# Orbiter_ENCODER_V4_0.net
KiCad netlist of a schematic drawn in EAGLE
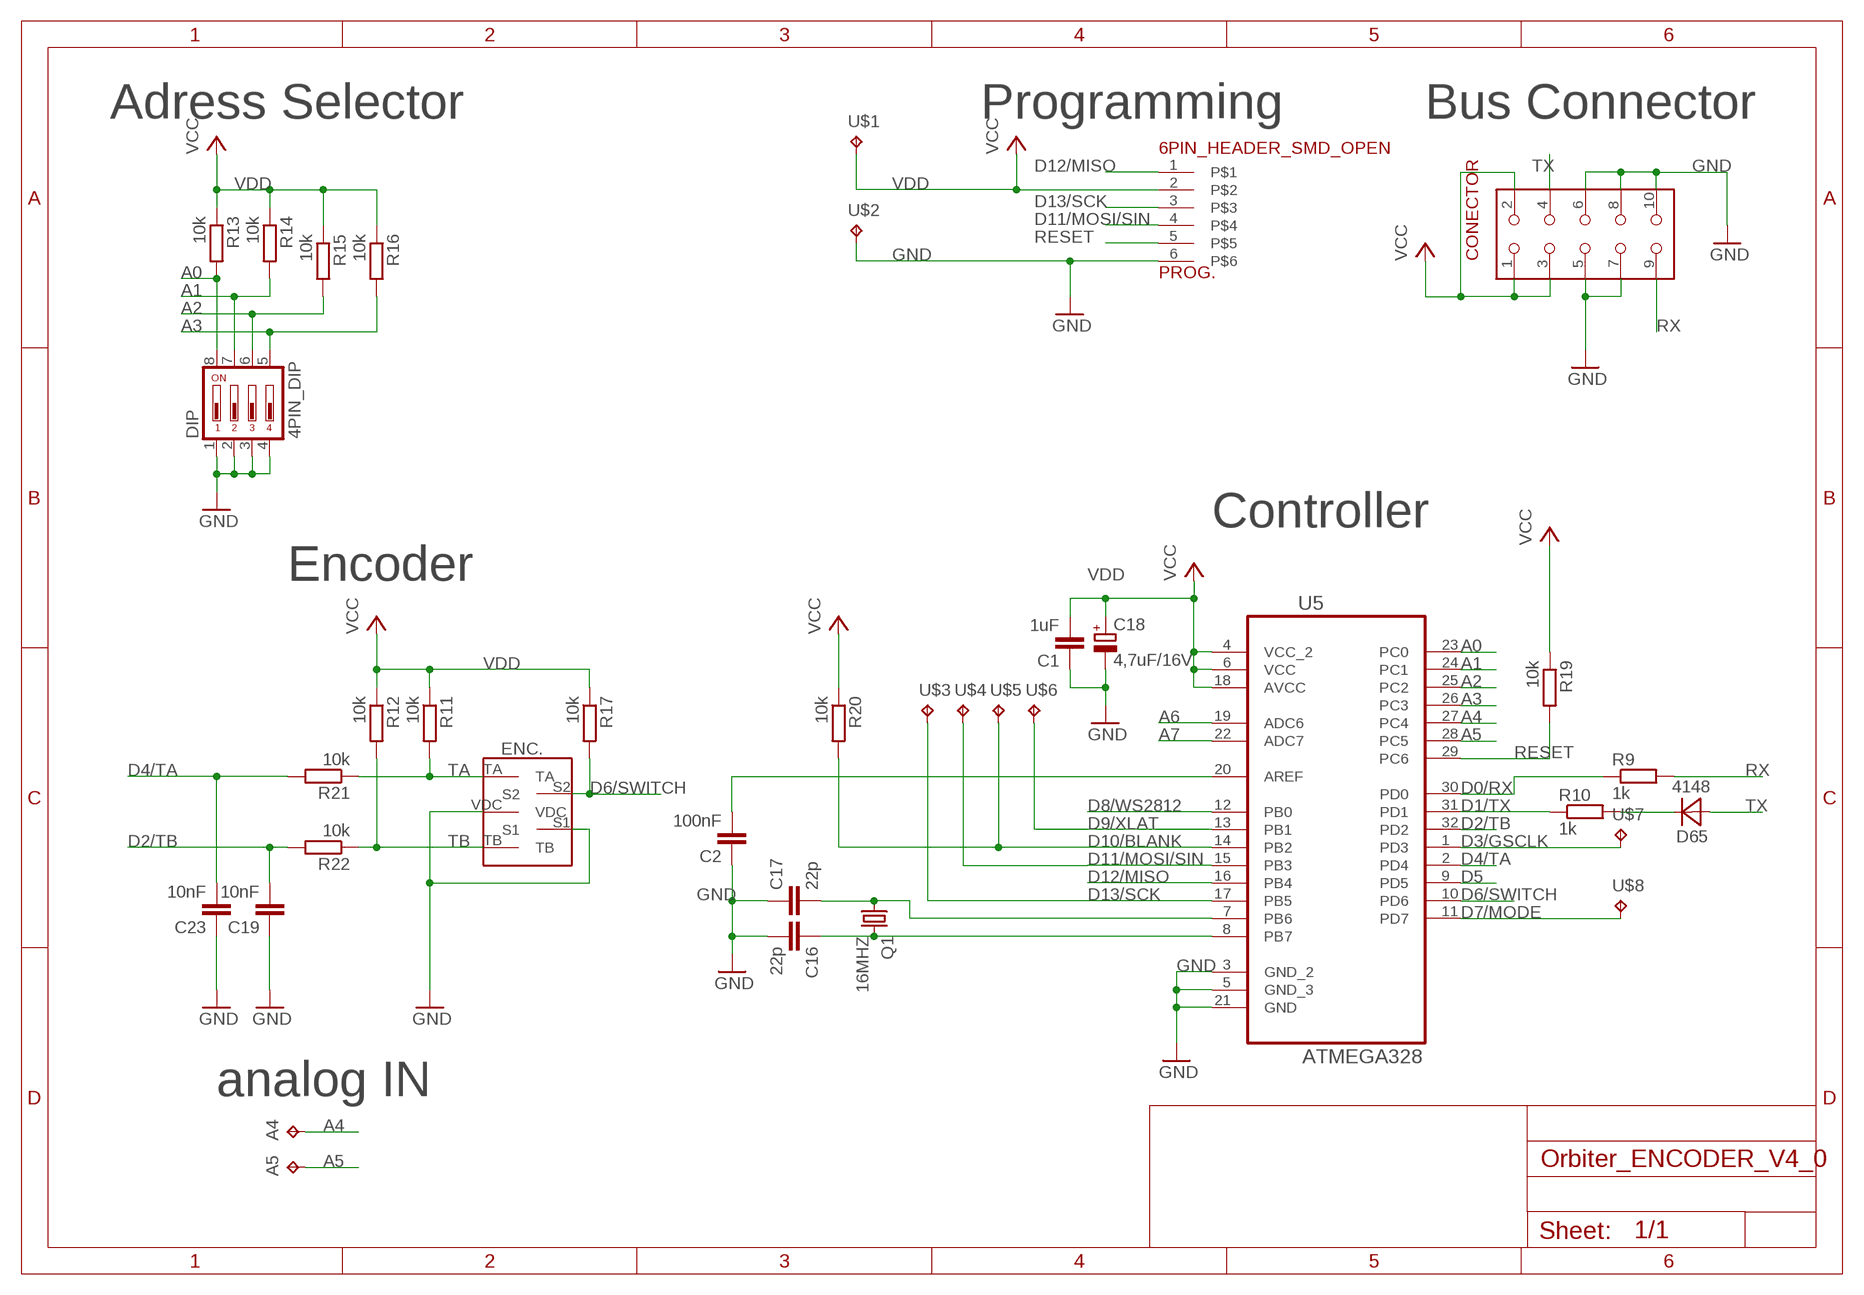
[diagram p0: schematic, sheet 1]

(export (version "E")
  (design (tool "Eeschema 10.0.6"))
  (components
    (comp (ref "A4")
      (value "TP")
      (footprint "eagle-import:OVAL_PAD")
      (libsource (lib "eagle-import") (part "TP"))
    )
    (comp (ref "A5")
      (value "TP")
      (footprint "eagle-import:OVAL_PAD")
      (libsource (lib "eagle-import") (part "TP"))
    )
    (comp (ref "C1")
      (value "1uF")
      (footprint "eagle-import:C0603")
      (libsource (lib "eagle-import") (part "CAPACITOR{dblquote}"))
    )
    (comp (ref "C2")
      (value "100nF")
      (footprint "eagle-import:C0603")
      (libsource (lib "eagle-import") (part "CAPACITOR{dblquote}"))
    )
    (comp (ref "C16")
      (value "22p")
      (footprint "eagle-import:C0603")
      (libsource (lib "eagle-import") (part "CAPACITOR{dblquote}"))
    )
    (comp (ref "C17")
      (value "22p")
      (footprint "eagle-import:C0603")
      (libsource (lib "eagle-import") (part "CAPACITOR{dblquote}"))
    )
    (comp (ref "C18")
      (value "4,7uF/16V")
      (footprint "eagle-import:153CLV-0605")
      (libsource (lib "eagle-import") (part "SMD_ELCTROLYTIC"))
    )
    (comp (ref "C19")
      (value "10nF")
      (footprint "eagle-import:C0603")
      (libsource (lib "eagle-import") (part "CAPACITOR{dblquote}"))
    )
    (comp (ref "C23")
      (value "10nF")
      (footprint "eagle-import:C0603")
      (libsource (lib "eagle-import") (part "CAPACITOR{dblquote}"))
    )
    (comp (ref "CONECTOR")
      (value "10PIN_HEADER_SMD")
      (footprint "eagle-import:87832-10")
      (libsource (lib "eagle-import") (part "10PIN_HEADER_SMD"))
    )
    (comp (ref "D65")
      (value "4148")
      (footprint "eagle-import:SOD323-R")
      (libsource (lib "eagle-import") (part "4148"))
    )
    (comp (ref "DIP")
      (value "4PIN_DIP")
      (footprint "eagle-import:CTS-219-04")
      (libsource (lib "eagle-import") (part "4PIN_DIP"))
    )
    (comp (ref "ENC.")
      (value "BOURNS_ENCODER")
      (footprint "eagle-import:BOURNS_ENCODER_SMD")
      (libsource (lib "eagle-import") (part "BOURNS_ENCODER"))
    )
    (comp (ref "PROG.")
      (value "6PIN_HEADER_SMD_OPEN")
      (footprint "eagle-import:6PIN_HEADER_SMD_OPEN")
      (libsource (lib "eagle-import") (part "6PIN_HEADER_SMD_OPEN"))
    )
    (comp (ref "Q1")
      (value "16MHZ")
      (footprint "eagle-import:SM49")
      (libsource (lib "eagle-import") (part "CRYSTAL_SM49"))
    )
    (comp (ref "R9")
      (value "1k")
      (footprint "eagle-import:R0805")
      (libsource (lib "eagle-import") (part "RESISTOR{dblquote}"))
    )
    (comp (ref "R10")
      (value "1k")
      (footprint "eagle-import:R0805")
      (libsource (lib "eagle-import") (part "RESISTOR{dblquote}"))
    )
    (comp (ref "R11")
      (value "10k")
      (footprint "eagle-import:R0805")
      (libsource (lib "eagle-import") (part "RESISTOR{dblquote}"))
    )
    (comp (ref "R12")
      (value "10k")
      (footprint "eagle-import:R0805")
      (libsource (lib "eagle-import") (part "RESISTOR{dblquote}"))
    )
    (comp (ref "R13")
      (value "10k")
      (footprint "eagle-import:R0805")
      (libsource (lib "eagle-import") (part "RESISTOR{dblquote}"))
    )
    (comp (ref "R14")
      (value "10k")
      (footprint "eagle-import:R0805")
      (libsource (lib "eagle-import") (part "RESISTOR{dblquote}"))
    )
    (comp (ref "R15")
      (value "10k")
      (footprint "eagle-import:R0805")
      (libsource (lib "eagle-import") (part "RESISTOR{dblquote}"))
    )
    (comp (ref "R16")
      (value "10k")
      (footprint "eagle-import:R0805")
      (libsource (lib "eagle-import") (part "RESISTOR{dblquote}"))
    )
    (comp (ref "R17")
      (value "10k")
      (footprint "eagle-import:R0805")
      (libsource (lib "eagle-import") (part "RESISTOR{dblquote}"))
    )
    (comp (ref "R19")
      (value "10k")
      (footprint "eagle-import:R0805")
      (libsource (lib "eagle-import") (part "RESISTOR{dblquote}"))
    )
    (comp (ref "R20")
      (value "10k")
      (footprint "eagle-import:R0805")
      (libsource (lib "eagle-import") (part "RESISTOR{dblquote}"))
    )
    (comp (ref "R21")
      (value "10k")
      (footprint "eagle-import:R0805")
      (libsource (lib "eagle-import") (part "RESISTOR{dblquote}"))
    )
    (comp (ref "R22")
      (value "10k")
      (footprint "eagle-import:R0805")
      (libsource (lib "eagle-import") (part "RESISTOR{dblquote}"))
    )
    (comp (ref "U$1")
      (value "TP")
      (footprint "eagle-import:OVAL_PAD")
      (libsource (lib "eagle-import") (part "TP"))
    )
    (comp (ref "U$2")
      (value "TP")
      (footprint "eagle-import:OVAL_PAD")
      (libsource (lib "eagle-import") (part "TP"))
    )
    (comp (ref "U$3")
      (value "TP")
      (footprint "eagle-import:OVAL_PAD")
      (libsource (lib "eagle-import") (part "TP"))
    )
    (comp (ref "U$4")
      (value "TP")
      (footprint "eagle-import:OVAL_PAD")
      (libsource (lib "eagle-import") (part "TP"))
    )
    (comp (ref "U$5")
      (value "TP")
      (footprint "eagle-import:OVAL_PAD")
      (libsource (lib "eagle-import") (part "TP"))
    )
    (comp (ref "U$6")
      (value "TP")
      (footprint "eagle-import:OVAL_PAD")
      (libsource (lib "eagle-import") (part "TP"))
    )
    (comp (ref "U$7")
      (value "TP")
      (footprint "eagle-import:OVAL_PAD")
      (libsource (lib "eagle-import") (part "TP"))
    )
    (comp (ref "U$8")
      (value "TP")
      (footprint "eagle-import:OVAL_PAD")
      (libsource (lib "eagle-import") (part "TP"))
    )
    (comp (ref "U5")
      (value "ATMEGA328")
      (footprint "eagle-import:QFP80P900X900X120-32N")
      (fields (field (name "MPN") "ATMEGA328P-AU"))
      (libsource (lib "eagle-import") (part "ATMEGA328P-AU"))
    )
  )
  (nets
    (net (code "1") (name "/A0") (class "Default")
      (node (ref "DIP") (pin "8") (pinfunction "8_8") (pintype "passive"))
      (node (ref "R13") (pin "2") (pinfunction "2_2") (pintype "passive"))
      (node (ref "U5") (pin "23") (pinfunction "PC0_23") (pintype "bidirectional"))
    )
    (net (code "2") (name "/A1") (class "Default")
      (node (ref "DIP") (pin "7") (pinfunction "7_7") (pintype "passive"))
      (node (ref "R14") (pin "2") (pinfunction "2_2") (pintype "passive"))
      (node (ref "U5") (pin "24") (pinfunction "PC1_24") (pintype "bidirectional"))
    )
    (net (code "3") (name "/A2") (class "Default")
      (node (ref "DIP") (pin "6") (pinfunction "6_6") (pintype "passive"))
      (node (ref "R15") (pin "2") (pinfunction "2_2") (pintype "passive"))
      (node (ref "U5") (pin "25") (pinfunction "PC2_25") (pintype "bidirectional"))
    )
    (net (code "4") (name "/A3") (class "Default")
      (node (ref "DIP") (pin "5") (pinfunction "5_5") (pintype "passive"))
      (node (ref "R16") (pin "2") (pinfunction "2_2") (pintype "passive"))
      (node (ref "U5") (pin "26") (pinfunction "PC3_26") (pintype "bidirectional"))
    )
    (net (code "5") (name "/A4") (class "Default")
      (node (ref "A4") (pin "P$1") (pinfunction "TP_P$1") (pintype "input"))
      (node (ref "U5") (pin "27") (pinfunction "PC4_27") (pintype "bidirectional"))
    )
    (net (code "6") (name "/A5") (class "Default")
      (node (ref "A5") (pin "P$1") (pinfunction "TP_P$1") (pintype "input"))
      (node (ref "U5") (pin "28") (pinfunction "PC5_28") (pintype "bidirectional"))
    )
    (net (code "7") (name "/A6") (class "Default")
      (node (ref "U5") (pin "19") (pinfunction "ADC6_19") (pintype "input"))
    )
    (net (code "8") (name "/A7") (class "Default")
      (node (ref "U5") (pin "22") (pinfunction "ADC7_22") (pintype "input"))
    )
    (net (code "9") (name "/D0{slash}RX") (class "Default")
      (node (ref "R9") (pin "1") (pinfunction "1_1") (pintype "passive"))
      (node (ref "U5") (pin "30") (pinfunction "PD0_30") (pintype "bidirectional"))
    )
    (net (code "10") (name "/D1{slash}TX") (class "Default")
      (node (ref "R10") (pin "1") (pinfunction "1_1") (pintype "passive"))
      (node (ref "U5") (pin "31") (pinfunction "PD1_31") (pintype "bidirectional"))
    )
    (net (code "11") (name "/D2{slash}TB") (class "Default")
      (node (ref "C19") (pin "2") (pinfunction "2_2") (pintype "passive"))
      (node (ref "R22") (pin "2") (pinfunction "2_2") (pintype "passive"))
      (node (ref "U5") (pin "32") (pinfunction "PD2_32") (pintype "bidirectional"))
    )
    (net (code "12") (name "/D3{slash}GSCLK") (class "Default")
      (node (ref "U$7") (pin "P$1") (pinfunction "TP_P$1") (pintype "input"))
      (node (ref "U5") (pin "1") (pinfunction "PD3_1") (pintype "bidirectional"))
    )
    (net (code "13") (name "/D4{slash}TA") (class "Default")
      (node (ref "C23") (pin "2") (pinfunction "2_2") (pintype "passive"))
      (node (ref "R21") (pin "2") (pinfunction "2_2") (pintype "passive"))
      (node (ref "U5") (pin "2") (pinfunction "PD4_2") (pintype "bidirectional"))
    )
    (net (code "14") (name "/D5") (class "Default")
      (node (ref "U5") (pin "9") (pinfunction "PD5_9") (pintype "bidirectional"))
    )
    (net (code "15") (name "/D6{slash}SWITCH") (class "Default")
      (node (ref "ENC.") (pin "S2") (pinfunction "S2_S2") (pintype "bidirectional"))
      (node (ref "R17") (pin "2") (pinfunction "2_2") (pintype "passive"))
      (node (ref "U5") (pin "10") (pinfunction "PD6_10") (pintype "bidirectional"))
    )
    (net (code "16") (name "/D7{slash}MODE") (class "Default")
      (node (ref "U$8") (pin "P$1") (pinfunction "TP_P$1") (pintype "input"))
      (node (ref "U5") (pin "11") (pinfunction "PD7_11") (pintype "bidirectional"))
    )
    (net (code "17") (name "/D8{slash}WS2812") (class "Default")
      (node (ref "U5") (pin "12") (pinfunction "PB0_12") (pintype "bidirectional"))
    )
    (net (code "18") (name "/D9{slash}XLAT") (class "Default")
      (node (ref "U$6") (pin "P$1") (pinfunction "TP_P$1") (pintype "input"))
      (node (ref "U5") (pin "13") (pinfunction "PB1_13") (pintype "bidirectional"))
    )
    (net (code "19") (name "/D10{slash}BLANK") (class "Default")
      (node (ref "R20") (pin "2") (pinfunction "2_2") (pintype "passive"))
      (node (ref "U$5") (pin "P$1") (pinfunction "TP_P$1") (pintype "input"))
      (node (ref "U5") (pin "14") (pinfunction "PB2_14") (pintype "bidirectional"))
    )
    (net (code "20") (name "/D11{slash}MOSI{slash}SIN") (class "Default")
      (node (ref "PROG.") (pin "4") (pinfunction "P$4_4") (pintype "bidirectional"))
      (node (ref "U$4") (pin "P$1") (pinfunction "TP_P$1") (pintype "input"))
      (node (ref "U5") (pin "15") (pinfunction "PB3_15") (pintype "bidirectional"))
    )
    (net (code "21") (name "/D12{slash}MISO") (class "Default")
      (node (ref "PROG.") (pin "1") (pinfunction "P$1_1") (pintype "bidirectional"))
      (node (ref "U5") (pin "16") (pinfunction "PB4_16") (pintype "bidirectional"))
    )
    (net (code "22") (name "/D13{slash}SCK") (class "Default")
      (node (ref "PROG.") (pin "3") (pinfunction "P$3_3") (pintype "bidirectional"))
      (node (ref "U$3") (pin "P$1") (pinfunction "TP_P$1") (pintype "input"))
      (node (ref "U5") (pin "17") (pinfunction "PB5_17") (pintype "bidirectional"))
    )
    (net (code "23") (name "/RESET") (class "Default")
      (node (ref "PROG.") (pin "5") (pinfunction "P$5_5") (pintype "bidirectional"))
      (node (ref "R19") (pin "2") (pinfunction "2_2") (pintype "passive"))
      (node (ref "U5") (pin "29") (pinfunction "PC6_29") (pintype "bidirectional"))
    )
    (net (code "24") (name "/RX") (class "Default")
      (node (ref "CONECTOR") (pin "9") (pinfunction "P$9_9") (pintype "bidirectional"))
      (node (ref "R9") (pin "2") (pinfunction "2_2") (pintype "passive"))
    )
    (net (code "25") (name "/TA") (class "Default")
      (node (ref "ENC.") (pin "TA") (pinfunction "TA_TA") (pintype "bidirectional"))
      (node (ref "R11") (pin "2") (pinfunction "2_2") (pintype "passive"))
      (node (ref "R21") (pin "1") (pinfunction "1_1") (pintype "passive"))
    )
    (net (code "26") (name "/TB") (class "Default")
      (node (ref "ENC.") (pin "TB") (pinfunction "TB_TB") (pintype "bidirectional"))
      (node (ref "R12") (pin "2") (pinfunction "2_2") (pintype "passive"))
      (node (ref "R22") (pin "1") (pinfunction "1_1") (pintype "passive"))
    )
    (net (code "27") (name "/TX") (class "Default")
      (node (ref "CONECTOR") (pin "4") (pinfunction "P$4_4") (pintype "bidirectional"))
      (node (ref "D65") (pin "A") (pinfunction "A_A") (pintype "passive"))
    )
    (net (code "28") (name "GND") (class "Default")
      (node (ref "C1") (pin "1") (pinfunction "1_1") (pintype "passive"))
      (node (ref "C16") (pin "2") (pinfunction "2_2") (pintype "passive"))
      (node (ref "C17") (pin "1") (pinfunction "1_1") (pintype "passive"))
      (node (ref "C18") (pin "-") (pinfunction "-_-") (pintype "passive"))
      (node (ref "C19") (pin "1") (pinfunction "1_1") (pintype "passive"))
      (node (ref "C2") (pin "1") (pinfunction "1_1") (pintype "passive"))
      (node (ref "C23") (pin "1") (pinfunction "1_1") (pintype "passive"))
      (node (ref "CONECTOR") (pin "10") (pinfunction "P$10_10") (pintype "bidirectional"))
      (node (ref "CONECTOR") (pin "5") (pinfunction "P$5_5") (pintype "bidirectional"))
      (node (ref "CONECTOR") (pin "6") (pinfunction "P$6_6") (pintype "bidirectional"))
      (node (ref "CONECTOR") (pin "7") (pinfunction "P$7_7") (pintype "bidirectional"))
      (node (ref "CONECTOR") (pin "8") (pinfunction "P$8_8") (pintype "bidirectional"))
      (node (ref "DIP") (pin "1") (pinfunction "1_1") (pintype "passive"))
      (node (ref "DIP") (pin "2") (pinfunction "2_2") (pintype "passive"))
      (node (ref "DIP") (pin "3") (pinfunction "3_3") (pintype "passive"))
      (node (ref "DIP") (pin "4") (pinfunction "4_4") (pintype "passive"))
      (node (ref "ENC.") (pin "S1") (pinfunction "S1_S1") (pintype "bidirectional"))
      (node (ref "ENC.") (pin "VDC") (pinfunction "VDC_VDC") (pintype "bidirectional"))
      (node (ref "PROG.") (pin "6") (pinfunction "P$6_6") (pintype "bidirectional"))
      (node (ref "U$2") (pin "P$1") (pinfunction "TP_P$1") (pintype "input"))
      (node (ref "U5") (pin "21") (pinfunction "GND_21") (pintype "passive"))
      (node (ref "U5") (pin "3") (pinfunction "GND_2_3") (pintype "passive"))
      (node (ref "U5") (pin "5") (pinfunction "GND_3_5") (pintype "passive"))
    )
    (net (code "29") (name "Net-(D65-PadC)") (class "Default")
      (node (ref "D65") (pin "C") (pinfunction "C_C") (pintype "passive"))
      (node (ref "R10") (pin "2") (pinfunction "2_2") (pintype "passive"))
    )
    (net (code "30") (name "Net-(U5-AREF)") (class "Default")
      (node (ref "C2") (pin "2") (pinfunction "2_2") (pintype "passive"))
      (node (ref "U5") (pin "20") (pinfunction "AREF_20") (pintype "input"))
    )
    (net (code "31") (name "Net-(U5-PB6)") (class "Default")
      (node (ref "C17") (pin "2") (pinfunction "2_2") (pintype "passive"))
      (node (ref "Q1") (pin "1") (pinfunction "1_1") (pintype "passive"))
      (node (ref "U5") (pin "7") (pinfunction "PB6_7") (pintype "bidirectional"))
    )
    (net (code "32") (name "Net-(U5-PB7)") (class "Default")
      (node (ref "C16") (pin "1") (pinfunction "1_1") (pintype "passive"))
      (node (ref "Q1") (pin "2") (pinfunction "2_2") (pintype "passive"))
      (node (ref "U5") (pin "8") (pinfunction "PB7_8") (pintype "bidirectional"))
    )
    (net (code "33") (name "VCC") (class "Default")
      (node (ref "C1") (pin "2") (pinfunction "2_2") (pintype "passive"))
      (node (ref "C18") (pin "+") (pinfunction "+_+") (pintype "passive"))
      (node (ref "CONECTOR") (pin "1") (pinfunction "P$1_1") (pintype "bidirectional"))
      (node (ref "CONECTOR") (pin "2") (pinfunction "P$2_2") (pintype "bidirectional"))
      (node (ref "CONECTOR") (pin "3") (pinfunction "P$3_3") (pintype "bidirectional"))
      (node (ref "PROG.") (pin "2") (pinfunction "P$2_2") (pintype "bidirectional"))
      (node (ref "R11") (pin "1") (pinfunction "1_1") (pintype "passive"))
      (node (ref "R12") (pin "1") (pinfunction "1_1") (pintype "passive"))
      (node (ref "R13") (pin "1") (pinfunction "1_1") (pintype "passive"))
      (node (ref "R14") (pin "1") (pinfunction "1_1") (pintype "passive"))
      (node (ref "R15") (pin "1") (pinfunction "1_1") (pintype "passive"))
      (node (ref "R16") (pin "1") (pinfunction "1_1") (pintype "passive"))
      (node (ref "R17") (pin "1") (pinfunction "1_1") (pintype "passive"))
      (node (ref "R19") (pin "1") (pinfunction "1_1") (pintype "passive"))
      (node (ref "R20") (pin "1") (pinfunction "1_1") (pintype "passive"))
      (node (ref "U$1") (pin "P$1") (pinfunction "TP_P$1") (pintype "input"))
      (node (ref "U5") (pin "18") (pinfunction "AVCC_18") (pintype "power_in"))
      (node (ref "U5") (pin "4") (pinfunction "VCC_2_4") (pintype "power_in"))
      (node (ref "U5") (pin "6") (pinfunction "VCC_6") (pintype "power_in"))
    )
  )
)
